# GPS.net
KiCad netlist of a schematic drawn in Altium Designer
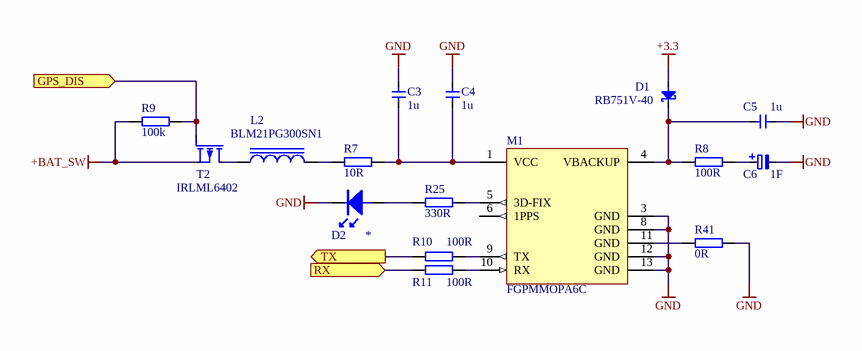
[diagram p0: GPS.SchDoc]

(export (version "E")
  (design (tool "Eeschema 10.0.6"))
  (components
    (comp (ref "C3")
      (value "1u")
      (footprint "C0805")
      (description "C; capacitor")
      (libsource (lib "SONEL_all") (part "C"))
    )
    (comp (ref "C4")
      (value "1u")
      (footprint "C0805")
      (description "C; capacitor")
      (libsource (lib "SONEL_all") (part "C"))
    )
    (comp (ref "C5")
      (value "1u")
      (footprint "C0805")
      (description "C; capacitor")
      (libsource (lib "SONEL_all") (part "C"))
    )
    (comp (ref "C6")
      (value "1F")
      (footprint "EECRG0V105H")
      (description "C; Polarized Capacitor")
      (libsource (lib "sch") (part "C_pol"))
    )
    (comp (ref "D1")
      (value "RB751V-40")
      (footprint "SOD323")
      (description "DS; Schottky Rectifier")
      (libsource (lib "SONEL_all") (part "RB751V-40"))
    )
    (comp (ref "D2")
      (value "*")
      (footprint "LED_0805")
      (description "LED;")
      (libsource (lib "SONEL_all") (part "LED"))
    )
    (comp (ref "L2")
      (value "BLM21PG300SN1")
      (footprint "L0805")
      (description "L;")
      (libsource (lib "SONEL_all") (part "BLM21PG300SN1"))
    )
    (comp (ref "M1")
      (value "FGPMMOPA6C")
      (footprint "FGPMMOPA6C")
      (description "GPS")
      (libsource (lib "sch") (part "FGPMMOPA6C"))
    )
    (comp (ref "R7")
      (value "10R")
      (footprint "R0805")
      (description "R; resistor")
      (libsource (lib "SONEL_all") (part "R"))
    )
    (comp (ref "R8")
      (value "100R")
      (footprint "R0805")
      (description "R; resistor")
      (libsource (lib "SONEL_all") (part "R"))
    )
    (comp (ref "R9")
      (value "100k")
      (footprint "R0805")
      (description "R; resistor")
      (libsource (lib "SONEL_all") (part "R"))
    )
    (comp (ref "R10")
      (value "100R")
      (footprint "R0805")
      (description "R; resistor")
      (libsource (lib "SONEL_all") (part "R"))
    )
    (comp (ref "R11")
      (value "100R")
      (footprint "R0805")
      (description "R; resistor")
      (libsource (lib "SONEL_all") (part "R"))
    )
    (comp (ref "R25")
      (value "330R")
      (footprint "R0805")
      (description "R; resistor")
      (libsource (lib "SONEL_all") (part "R"))
    )
    (comp (ref "R41")
      (value "0R")
      (footprint "R0805")
      (description "R; resistor")
      (libsource (lib "SONEL_all") (part "R"))
    )
    (comp (ref "T2")
      (value "IRLML6402")
      (footprint "MICRO3")
      (description "T_M_P; P-Channel MOSFET")
      (libsource (lib "SONEL_all") (part "IRLML6402"))
    )
  )
  (nets
    (net (code "1") (name "+3.3") (class "Default")
      (node (ref "D1") (pin "A") (pinfunction "A_A") (pintype "passive"))
    )
    (net (code "2") (name "+BAT_SW") (class "Default")
      (node (ref "R9") (pin "2") (pintype "passive"))
      (node (ref "T2") (pin "S") (pinfunction "S_S") (pintype "passive"))
    )
    (net (code "3") (name "/GPS_DIS") (class "Default")
      (node (ref "R9") (pin "1") (pintype "passive"))
      (node (ref "T2") (pin "G") (pinfunction "G_G") (pintype "passive"))
    )
    (net (code "4") (name "/RX") (class "Default") (node (ref "R11") (pin "2") (pintype "passive")))
    (net (code "5") (name "/TX") (class "Default") (node (ref "R10") (pin "2") (pintype "passive")))
    (net (code "6") (name "GND") (class "Default")
      (node (ref "C3") (pin "1") (pintype "passive"))
      (node (ref "C4") (pin "1") (pintype "passive"))
      (node (ref "C5") (pin "1") (pintype "passive"))
      (node (ref "C6") (pin "-") (pinfunction "2_-") (pintype "passive"))
      (node (ref "D2") (pin "K") (pinfunction "K_K") (pintype "passive"))
      (node (ref "M1") (pin "12") (pinfunction "GND_12") (pintype "power_in"))
      (node (ref "M1") (pin "13") (pinfunction "GND_13") (pintype "power_in"))
      (node (ref "M1") (pin "3") (pinfunction "GND_3") (pintype "power_in"))
      (node (ref "M1") (pin "8") (pinfunction "GND_8") (pintype "power_in"))
      (node (ref "R41") (pin "1") (pintype "passive"))
    )
    (net (code "7") (name "Net-(C6-1)") (class "Default")
      (node (ref "C6") (pin "+") (pinfunction "1_+") (pintype "passive"))
      (node (ref "R8") (pin "1") (pintype "passive"))
    )
    (net (code "8") (name "Net-(D2-PadA)") (class "Default")
      (node (ref "D2") (pin "A") (pinfunction "A_A") (pintype "passive"))
      (node (ref "R25") (pin "2") (pintype "passive"))
    )
    (net (code "9") (name "Net-(L2-Pad1)") (class "Default")
      (node (ref "L2") (pin "1") (pinfunction "1_1") (pintype "passive"))
      (node (ref "T2") (pin "D") (pinfunction "D_D") (pintype "passive"))
    )
    (net (code "10") (name "Net-(L2-Pad2)") (class "Default")
      (node (ref "L2") (pin "2") (pinfunction "2_2") (pintype "passive"))
      (node (ref "R7") (pin "2") (pintype "passive"))
    )
    (net (code "11") (name "Net-(M1-3D-FIX)") (class "Default")
      (node (ref "M1") (pin "5") (pinfunction "3D-FIX_5") (pintype "output"))
      (node (ref "R25") (pin "1") (pintype "passive"))
    )
    (net (code "12") (name "Net-(M1-GND-Pad11)") (class "Default")
      (node (ref "M1") (pin "11") (pinfunction "GND_11") (pintype "power_in"))
      (node (ref "R41") (pin "2") (pintype "passive"))
    )
    (net (code "13") (name "Net-(M1-RX)") (class "Default")
      (node (ref "M1") (pin "10") (pinfunction "RX_10") (pintype "input"))
      (node (ref "R11") (pin "1") (pintype "passive"))
    )
    (net (code "14") (name "Net-(M1-TX)") (class "Default")
      (node (ref "M1") (pin "9") (pinfunction "TX_9") (pintype "output"))
      (node (ref "R10") (pin "1") (pintype "passive"))
    )
    (net (code "15") (name "Net-(M1-VBACKUP)") (class "Default")
      (node (ref "C5") (pin "2") (pintype "passive"))
      (node (ref "D1") (pin "K") (pinfunction "K_K") (pintype "passive"))
      (node (ref "M1") (pin "4") (pinfunction "VBACKUP_4") (pintype "power_in"))
      (node (ref "R8") (pin "2") (pintype "passive"))
    )
    (net (code "16") (name "Net-(M1-VCC)") (class "Default")
      (node (ref "C3") (pin "2") (pintype "passive"))
      (node (ref "C4") (pin "2") (pintype "passive"))
      (node (ref "M1") (pin "1") (pinfunction "VCC_1") (pintype "power_in"))
      (node (ref "R7") (pin "1") (pintype "passive"))
    )
    (net (code "17") (name "unconnected-(M1-1PPS-Pad6)") (class "Default")
      (node (ref "M1") (pin "6") (pinfunction "1PPS_6") (pintype "output"))
    )
  )
)
